# POWER.net
KiCad netlist of a schematic drawn in Altium Designer
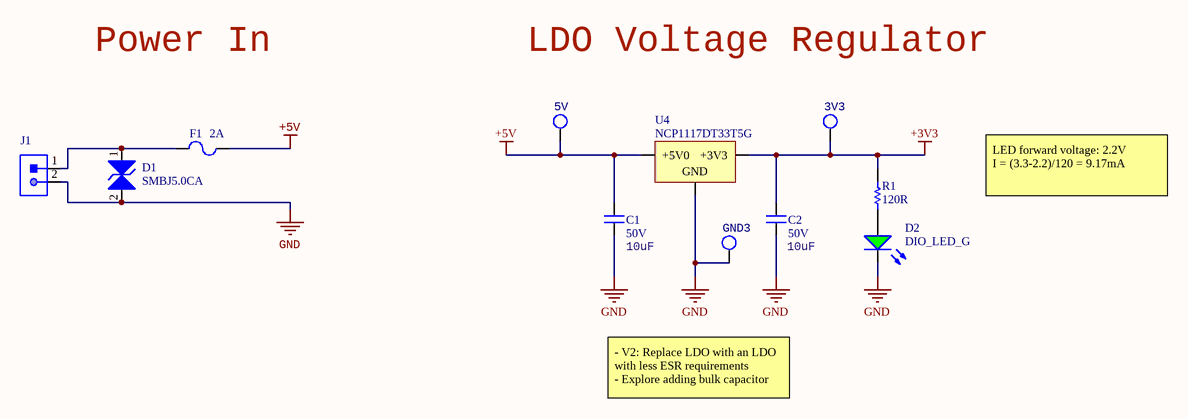
[diagram p0: POWER.SchDoc]

(export (version "E")
  (design (tool "Eeschema 10.0.6"))
  (components
    (comp (ref "3V3")
      (value "TESTPOINT_LOOP")
      (footprint "TESTPOINT_LOOP")
      (description "Loop testpoint through-hole pad")
      (fields (field (name "MANUFACTURER") "Keystone Electronics"))
      (libsource (lib "UWRT_Schematic_Library_2020") (part "TESTPOINT_LOOP"))
    )
    (comp (ref "5V")
      (value "TESTPOINT_LOOP")
      (footprint "TESTPOINT_LOOP")
      (description "Loop testpoint through-hole pad")
      (fields (field (name "MANUFACTURER") "Keystone Electronics"))
      (libsource (lib "UWRT_Schematic_Library_2020") (part "TESTPOINT_LOOP"))
    )
    (comp (ref "C1")
      (value "10uF")
      (footprint "CAPC1206(3216)")
      (description "CAP CER 10UF 50V X5R 1206")
      (fields
        (field (name "MPN") "GRT31CR61H106KE01L")
        (field (name "MANUFACTURER") "Murata")
        (field (name "VOLTAGE RATING") "50V")
      )
      (libsource (lib "UWRT_Schematic_Library_2020") (part "CAP_10uF_50V_1206"))
    )
    (comp (ref "C2")
      (value "10uF")
      (footprint "CAPC1206(3216)")
      (description "CAP CER 10UF 50V X5R 1206")
      (fields
        (field (name "MPN") "GRT31CR61H106KE01L")
        (field (name "MANUFACTURER") "Murata")
        (field (name "VOLTAGE RATING") "50V")
      )
      (libsource (lib "UWRT_Schematic_Library_2020") (part "CAP_10uF_50V_1206"))
    )
    (comp (ref "D1")
      (value "TVS_DIODE_BIDIRECTIONAL")
      (footprint "TVS_DIODE_BIDIRECTIONAL")
      (description "TVS DIODE 5V 9.2V DO214AA")
      (fields (field (name "MANUFACTURER PART NUMBER 1") "SMBJ5.0CA"))
      (libsource (lib "UWRT_Schematic_Library_2020") (part "TVS_DIODE_BIDIRECTIONAL"))
    )
    (comp (ref "D2")
      (value "DIO_LED_G")
      (footprint "LED_0805_LINE")
      (description "LED GREEN DIFFUSED 0805 SMD")
      (fields (field (name "MPN") "LG R971-KN-1") (field (name "MANUFACTURER") "OSRAM"))
      (libsource (lib "UWRT_Schematic_Library_2020") (part "DIO_LED_G"))
    )
    (comp (ref "F1")
      (value "FUSE_2A_0603")
      (footprint "FUSE_0603")
      (description "FUSE SMD 2A 32V")
      (fields (field (name "CURRENT RATING") "2A"))
      (libsource (lib "UWRT_Schematic_Library_2020") (part "FUSE_2A_0603"))
    )
    (comp (ref "GND3")
      (value "TESTPOINT_LOOP")
      (footprint "TESTPOINT_LOOP")
      (description "Loop testpoint through-hole pad")
      (fields (field (name "MANUFACTURER") "Keystone Electronics"))
      (libsource (lib "UWRT_Schematic_Library_2020") (part "TESTPOINT_LOOP"))
    )
    (comp (ref "J1")
      (value "CON_2M_SM4")
      (footprint "JST-B2B-SM4-TB")
      (description "CONN HEADER SMD 2POS 2MM")
      (fields
        (field (name "MANUFACTURER") "JST")
        (field (name "MANUFACTURER PART NUMBER") "B2B-PH-SM4-TB(LF)(SN)")
      )
      (libsource (lib "UWRT_Schematic_Library_2020") (part "CON_2M_SM4"))
    )
    (comp (ref "R1")
      (value "120R")
      (footprint "RESC0603(1608)_N")
      (description "RES SMD 120 OHM 5% 1/10W 0603")
      (fields (field (name "TOLERANCE") "5%") (field (name "MANUFACTURER") "Yageo"))
      (libsource (lib "UWRT_Schematic_Library_2020") (part "RES_120R_0603"))
    )
    (comp (ref "U4")
      (value "5V0_3V3_LDO")
      (footprint "VOLTAGE_REGULATOR")
      (description "IC REG LINEAR 3.3V 1A DPAK")
      (fields (field (name "MPN") "NCP1117DT33T5G") (field (name "MANUFACTURER") "ON Semiconductor"))
      (libsource (lib "UWRT_Schematic_Library_2020") (part "5V0_3V3_LDO"))
    )
  )
  (nets
    (net (code "1") (name "+3V3") (class "Default")
      (node (ref "3V3") (pin "1") (pintype "passive"))
      (node (ref "C2") (pin "1") (pinfunction "1_1") (pintype "passive"))
      (node (ref "R1") (pin "2") (pinfunction "2_2") (pintype "passive"))
      (node (ref "U4") (pin "2") (pinfunction "+3V3_2") (pintype "passive"))
    )
    (net (code "2") (name "+5V") (class "Default")
      (node (ref "5V") (pin "1") (pintype "passive"))
      (node (ref "C1") (pin "1") (pinfunction "1_1") (pintype "passive"))
      (node (ref "F1") (pin "2") (pinfunction "2_2") (pintype "passive"))
      (node (ref "U4") (pin "3") (pinfunction "+5V0_3") (pintype "passive"))
    )
    (net (code "3") (name "GND") (class "Default")
      (node (ref "C1") (pin "2") (pinfunction "2_2") (pintype "passive"))
      (node (ref "C2") (pin "2") (pinfunction "2_2") (pintype "passive"))
      (node (ref "D1") (pin "2") (pinfunction "2_2") (pintype "passive"))
      (node (ref "D2") (pin "2") (pinfunction "K_2") (pintype "passive"))
      (node (ref "GND3") (pin "1") (pintype "passive"))
      (node (ref "J1") (pin "2") (pinfunction "2_2") (pintype "passive"))
      (node (ref "U4") (pin "1") (pinfunction "GND_1") (pintype "passive"))
    )
    (net (code "4") (name "Net-(D1-Pad1)") (class "Default")
      (node (ref "D1") (pin "1") (pinfunction "1_1") (pintype "passive"))
      (node (ref "F1") (pin "1") (pinfunction "1_1") (pintype "passive"))
      (node (ref "J1") (pin "1") (pinfunction "1_1") (pintype "passive"))
    )
    (net (code "5") (name "Net-(D2-A)") (class "Default")
      (node (ref "D2") (pin "1") (pinfunction "A_1") (pintype "passive"))
      (node (ref "R1") (pin "1") (pinfunction "1_1") (pintype "passive"))
    )
  )
)
